# Adafruit_EZ-Key_Breakout.net
KiCad netlist of a schematic drawn in EAGLE
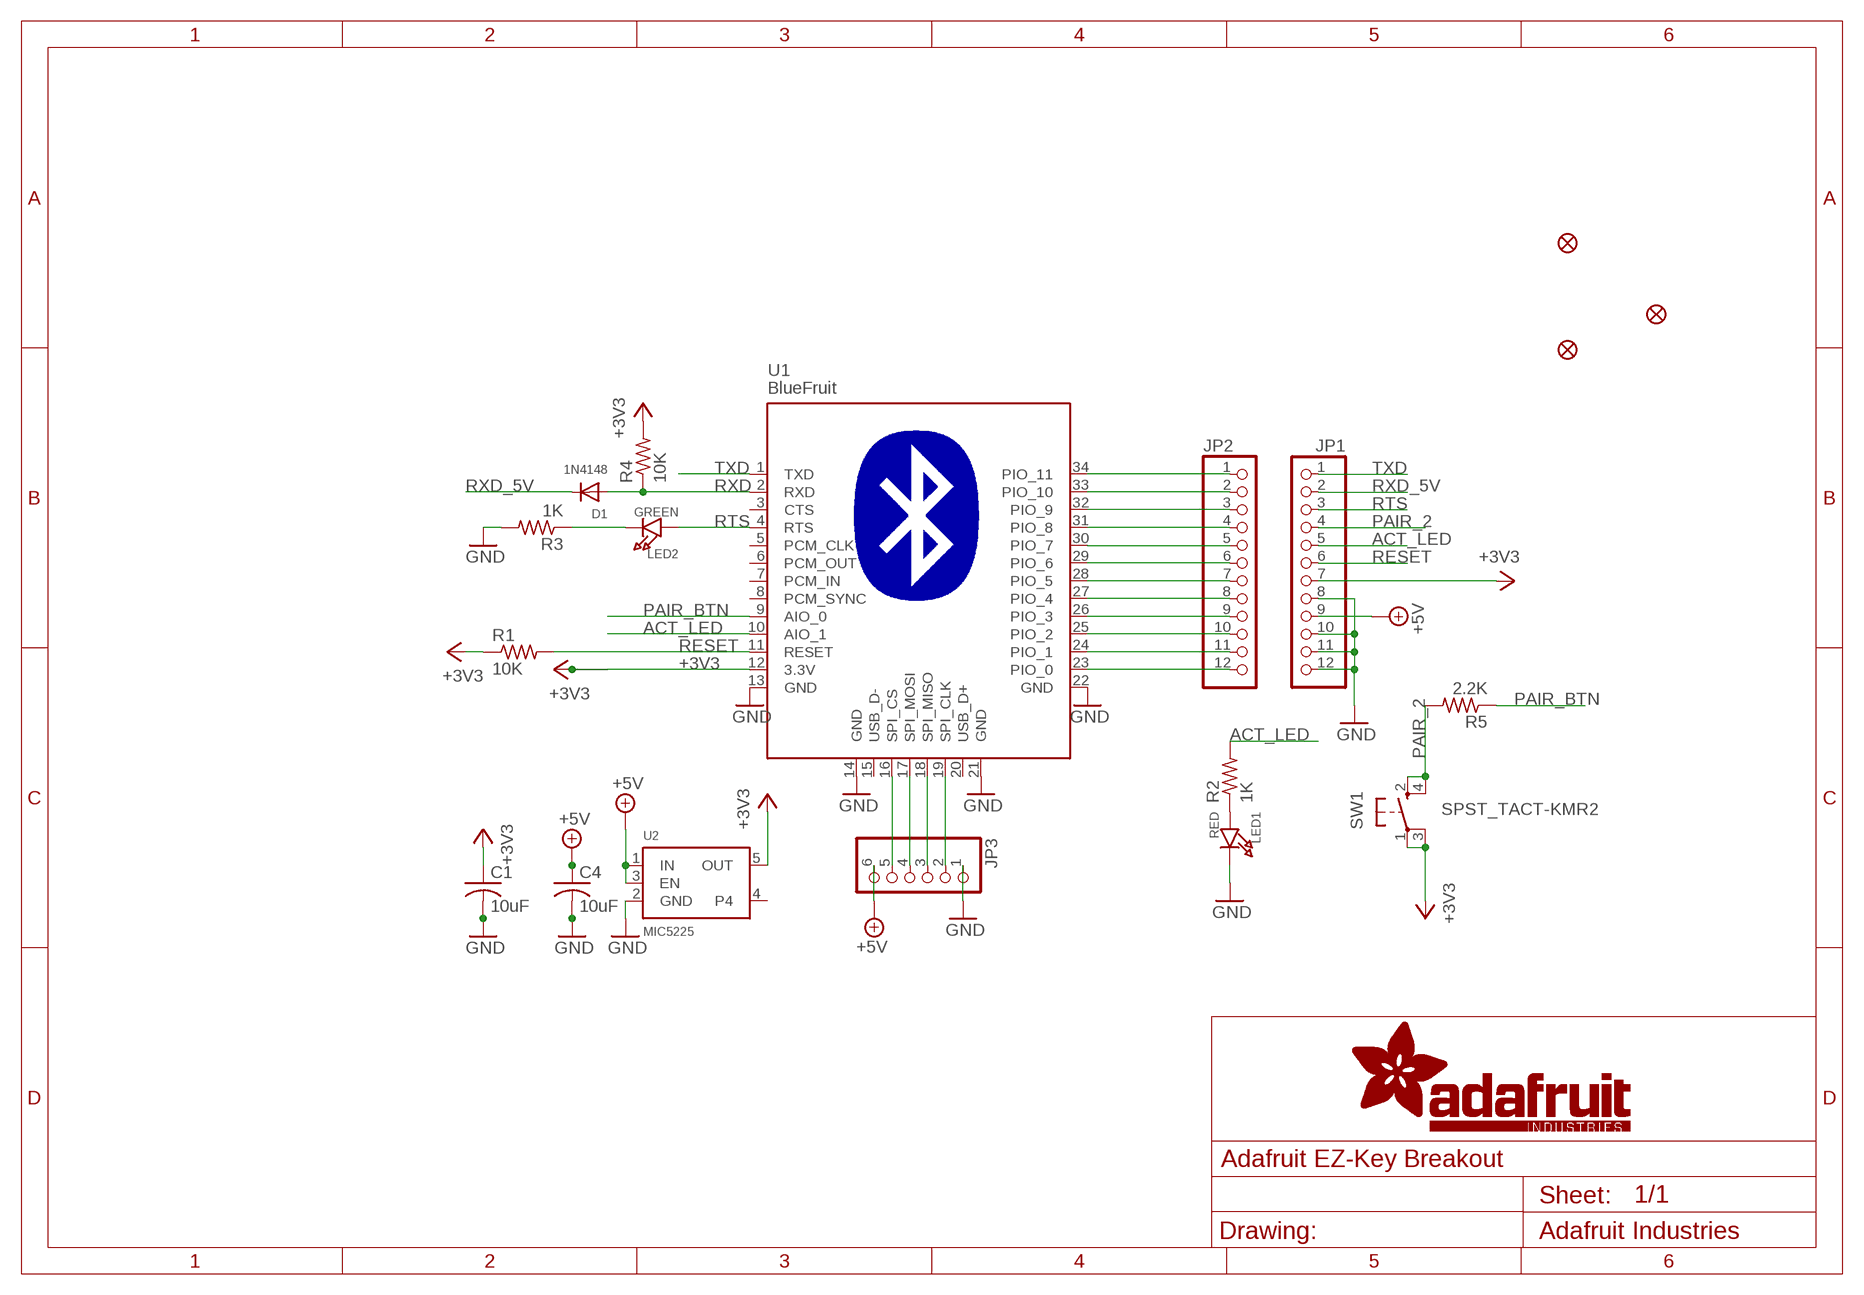
[diagram p0: schematic, sheet 1]

(export (version "E")
  (design (tool "Eeschema 10.0.6"))
  (components
    (comp (ref "C1")
      (value "10uF")
      (footprint "eagle-import:C0805")
      (libsource (lib "eagle-import") (part "C-USC0805"))
    )
    (comp (ref "C4")
      (value "10uF")
      (footprint "eagle-import:C0805")
      (libsource (lib "eagle-import") (part "C-USC0805"))
    )
    (comp (ref "D1")
      (value "1N4148")
      (footprint "eagle-import:SOD-323")
      (libsource (lib "eagle-import") (part "DIODESOD-323"))
    )
    (comp (ref "FID1")
      (value "FIDUCIAL\"\"")
      (footprint "eagle-import:FIDUCIAL_1MM")
      (libsource (lib "eagle-import") (part "FIDUCIAL{dblquote}{dblquote}"))
    )
    (comp (ref "FID2")
      (value "FIDUCIAL\"\"")
      (footprint "eagle-import:FIDUCIAL_1MM")
      (libsource (lib "eagle-import") (part "FIDUCIAL{dblquote}{dblquote}"))
    )
    (comp (ref "FID3")
      (value "FIDUCIAL\"\"")
      (footprint "eagle-import:FIDUCIAL_1MM")
      (libsource (lib "eagle-import") (part "FIDUCIAL{dblquote}{dblquote}"))
    )
    (comp (ref "JP1")
      (value "PINHD-1X12-CB")
      (footprint "eagle-import:1X12-CB")
      (libsource (lib "eagle-import") (part "PINHD-1X12-CB"))
    )
    (comp (ref "JP2")
      (value "PINHD-1X12-CB")
      (footprint "eagle-import:1X12-CB")
      (libsource (lib "eagle-import") (part "PINHD-1X12-CB"))
    )
    (comp (ref "JP3")
      (value "PINHD-1X6B")
      (footprint "eagle-import:1X06-BIG")
      (libsource (lib "eagle-import") (part "PINHD-1X6B"))
    )
    (comp (ref "LED1")
      (value "RED")
      (footprint "eagle-import:CHIPLED_0805_NOOUTLINE")
      (libsource (lib "eagle-import") (part "LED0805_NOOUTLINE"))
    )
    (comp (ref "LED2")
      (value "GREEN")
      (footprint "eagle-import:CHIPLED_0805_NOOUTLINE")
      (libsource (lib "eagle-import") (part "LED0805_NOOUTLINE"))
    )
    (comp (ref "R1")
      (value "10K")
      (footprint "eagle-import:R0805")
      (libsource (lib "eagle-import") (part "R-US_R0805"))
    )
    (comp (ref "R2")
      (value "1K")
      (footprint "eagle-import:R0805")
      (libsource (lib "eagle-import") (part "R-US_R0805"))
    )
    (comp (ref "R3")
      (value "1K")
      (footprint "eagle-import:R0805")
      (libsource (lib "eagle-import") (part "R-US_R0805"))
    )
    (comp (ref "R4")
      (value "10K")
      (footprint "eagle-import:R0805")
      (libsource (lib "eagle-import") (part "R-US_R0805"))
    )
    (comp (ref "R5")
      (value "2.2K")
      (footprint "eagle-import:R0805")
      (libsource (lib "eagle-import") (part "R-US_R0805"))
    )
    (comp (ref "SW1")
      (value "SPST_TACT-KMR2")
      (footprint "eagle-import:KMR2")
      (libsource (lib "eagle-import") (part "SPST_TACT-KMR2"))
    )
    (comp (ref "U1")
      (value "BlueFruit")
      (footprint "eagle-import:BLUETOOTH_MODULE")
      (libsource (lib "eagle-import") (part "BLUETOOTH_MODULE"))
    )
    (comp (ref "U2")
      (value "MIC5225")
      (footprint "eagle-import:SOT23-5")
      (libsource (lib "eagle-import") (part "VREG_SOT23-5"))
    )
  )
  (nets
    (net (code "1") (name "+3V3") (class "Default")
      (node (ref "C1") (pin "1") (pinfunction "1_1") (pintype "passive"))
      (node (ref "JP1") (pin "7") (pinfunction "7_7") (pintype "passive"))
      (node (ref "R1") (pin "1") (pinfunction "1_1") (pintype "passive"))
      (node (ref "R4") (pin "2") (pinfunction "2_2") (pintype "passive"))
      (node (ref "SW1") (pin "1") (pinfunction "P_1") (pintype "passive"))
      (node (ref "SW1") (pin "3") (pinfunction "P1_3") (pintype "passive"))
      (node (ref "U1") (pin "12") (pinfunction "3.3V_12") (pintype "power_in"))
      (node (ref "U2") (pin "5") (pinfunction "OUT_5") (pintype "power_in"))
    )
    (net (code "2") (name "+5V") (class "Default")
      (node (ref "C4") (pin "1") (pinfunction "1_1") (pintype "passive"))
      (node (ref "JP1") (pin "9") (pinfunction "9_9") (pintype "passive"))
      (node (ref "JP3") (pin "6") (pinfunction "6_6") (pintype "passive"))
      (node (ref "U2") (pin "1") (pinfunction "IN_1") (pintype "power_in"))
      (node (ref "U2") (pin "3") (pinfunction "EN_3") (pintype "input"))
    )
    (net (code "3") (name "/ACT_LED") (class "Default")
      (node (ref "JP1") (pin "5") (pinfunction "5_5") (pintype "passive"))
      (node (ref "R2") (pin "2") (pinfunction "2_2") (pintype "passive"))
      (node (ref "U1") (pin "10") (pinfunction "AIO_1_10") (pintype "bidirectional"))
    )
    (net (code "4") (name "/PAIR_2") (class "Default")
      (node (ref "JP1") (pin "4") (pinfunction "4_4") (pintype "passive"))
      (node (ref "R5") (pin "2") (pinfunction "2_2") (pintype "passive"))
      (node (ref "SW1") (pin "2") (pinfunction "S_2") (pintype "passive"))
      (node (ref "SW1") (pin "4") (pinfunction "S1_4") (pintype "passive"))
    )
    (net (code "5") (name "/PAIR_BTN") (class "Default")
      (node (ref "R5") (pin "1") (pinfunction "1_1") (pintype "passive"))
      (node (ref "U1") (pin "9") (pinfunction "AIO_0_9") (pintype "bidirectional"))
    )
    (net (code "6") (name "/RESET") (class "Default")
      (node (ref "JP1") (pin "6") (pinfunction "6_6") (pintype "passive"))
      (node (ref "R1") (pin "2") (pinfunction "2_2") (pintype "passive"))
      (node (ref "U1") (pin "11") (pinfunction "RESET_11") (pintype "bidirectional"))
    )
    (net (code "7") (name "/RTS") (class "Default")
      (node (ref "JP1") (pin "3") (pinfunction "3_3") (pintype "passive"))
      (node (ref "LED2") (pin "A") (pinfunction "A_A") (pintype "passive"))
      (node (ref "U1") (pin "4") (pinfunction "RTS_4") (pintype "bidirectional"))
    )
    (net (code "8") (name "/RXD") (class "Default")
      (node (ref "D1") (pin "A") (pinfunction "A_A") (pintype "passive"))
      (node (ref "R4") (pin "1") (pinfunction "1_1") (pintype "passive"))
      (node (ref "U1") (pin "2") (pinfunction "RXD_2") (pintype "bidirectional"))
    )
    (net (code "9") (name "/RXD_5V") (class "Default")
      (node (ref "D1") (pin "C") (pinfunction "C_C") (pintype "passive"))
      (node (ref "JP1") (pin "2") (pinfunction "2_2") (pintype "passive"))
    )
    (net (code "10") (name "/TXD") (class "Default")
      (node (ref "JP1") (pin "1") (pinfunction "1_1") (pintype "passive"))
      (node (ref "U1") (pin "1") (pinfunction "TXD_1") (pintype "bidirectional"))
    )
    (net (code "11") (name "GND") (class "Default")
      (node (ref "C1") (pin "2") (pinfunction "2_2") (pintype "passive"))
      (node (ref "C4") (pin "2") (pinfunction "2_2") (pintype "passive"))
      (node (ref "JP1") (pin "10") (pinfunction "10_10") (pintype "passive"))
      (node (ref "JP1") (pin "11") (pinfunction "11_11") (pintype "passive"))
      (node (ref "JP1") (pin "12") (pinfunction "12_12") (pintype "passive"))
      (node (ref "JP1") (pin "8") (pinfunction "8_8") (pintype "passive"))
      (node (ref "JP3") (pin "1") (pinfunction "1_1") (pintype "passive"))
      (node (ref "LED1") (pin "C") (pinfunction "C_C") (pintype "passive"))
      (node (ref "R3") (pin "2") (pinfunction "2_2") (pintype "passive"))
      (node (ref "U1") (pin "13") (pinfunction "GND_13") (pintype "power_in"))
      (node (ref "U1") (pin "14") (pinfunction "GND_14") (pintype "power_in"))
      (node (ref "U1") (pin "21") (pinfunction "GND_21") (pintype "power_in"))
      (node (ref "U1") (pin "22") (pinfunction "GND_22") (pintype "power_in"))
      (node (ref "U2") (pin "2") (pinfunction "GND_2") (pintype "power_in"))
    )
    (net (code "12") (name "Net-(LED1-PadA)") (class "Default")
      (node (ref "LED1") (pin "A") (pinfunction "A_A") (pintype "passive"))
      (node (ref "R2") (pin "1") (pinfunction "1_1") (pintype "passive"))
    )
    (net (code "13") (name "Net-(LED2-PadC)") (class "Default")
      (node (ref "LED2") (pin "C") (pinfunction "C_C") (pintype "passive"))
      (node (ref "R3") (pin "1") (pinfunction "1_1") (pintype "passive"))
    )
    (net (code "14") (name "Net-(U1-PIO_0)") (class "Default")
      (node (ref "JP2") (pin "12") (pinfunction "12_12") (pintype "passive"))
      (node (ref "U1") (pin "23") (pinfunction "PIO_0_23") (pintype "bidirectional"))
    )
    (net (code "15") (name "Net-(U1-PIO_1)") (class "Default")
      (node (ref "JP2") (pin "11") (pinfunction "11_11") (pintype "passive"))
      (node (ref "U1") (pin "24") (pinfunction "PIO_1_24") (pintype "bidirectional"))
    )
    (net (code "16") (name "Net-(U1-PIO_2)") (class "Default")
      (node (ref "JP2") (pin "10") (pinfunction "10_10") (pintype "passive"))
      (node (ref "U1") (pin "25") (pinfunction "PIO_2_25") (pintype "bidirectional"))
    )
    (net (code "17") (name "Net-(U1-PIO_3)") (class "Default")
      (node (ref "JP2") (pin "9") (pinfunction "9_9") (pintype "passive"))
      (node (ref "U1") (pin "26") (pinfunction "PIO_3_26") (pintype "bidirectional"))
    )
    (net (code "18") (name "Net-(U1-PIO_4)") (class "Default")
      (node (ref "JP2") (pin "8") (pinfunction "8_8") (pintype "passive"))
      (node (ref "U1") (pin "27") (pinfunction "PIO_4_27") (pintype "bidirectional"))
    )
    (net (code "19") (name "Net-(U1-PIO_5)") (class "Default")
      (node (ref "JP2") (pin "7") (pinfunction "7_7") (pintype "passive"))
      (node (ref "U1") (pin "28") (pinfunction "PIO_5_28") (pintype "bidirectional"))
    )
    (net (code "20") (name "Net-(U1-PIO_6)") (class "Default")
      (node (ref "JP2") (pin "6") (pinfunction "6_6") (pintype "passive"))
      (node (ref "U1") (pin "29") (pinfunction "PIO_6_29") (pintype "bidirectional"))
    )
    (net (code "21") (name "Net-(U1-PIO_7)") (class "Default")
      (node (ref "JP2") (pin "5") (pinfunction "5_5") (pintype "passive"))
      (node (ref "U1") (pin "30") (pinfunction "PIO_7_30") (pintype "bidirectional"))
    )
    (net (code "22") (name "Net-(U1-PIO_8)") (class "Default")
      (node (ref "JP2") (pin "4") (pinfunction "4_4") (pintype "passive"))
      (node (ref "U1") (pin "31") (pinfunction "PIO_8_31") (pintype "bidirectional"))
    )
    (net (code "23") (name "Net-(U1-PIO_9)") (class "Default")
      (node (ref "JP2") (pin "3") (pinfunction "3_3") (pintype "passive"))
      (node (ref "U1") (pin "32") (pinfunction "PIO_9_32") (pintype "bidirectional"))
    )
    (net (code "24") (name "Net-(U1-PIO_10)") (class "Default")
      (node (ref "JP2") (pin "2") (pinfunction "2_2") (pintype "passive"))
      (node (ref "U1") (pin "33") (pinfunction "PIO_10_33") (pintype "bidirectional"))
    )
    (net (code "25") (name "Net-(U1-PIO_11)") (class "Default")
      (node (ref "JP2") (pin "1") (pinfunction "1_1") (pintype "passive"))
      (node (ref "U1") (pin "34") (pinfunction "PIO_11_34") (pintype "bidirectional"))
    )
    (net (code "26") (name "Net-(U1-SPI_CLK)") (class "Default")
      (node (ref "JP3") (pin "2") (pinfunction "2_2") (pintype "passive"))
      (node (ref "U1") (pin "19") (pinfunction "SPI_CLK_19") (pintype "bidirectional"))
    )
    (net (code "27") (name "Net-(U1-SPI_CS)") (class "Default")
      (node (ref "JP3") (pin "5") (pinfunction "5_5") (pintype "passive"))
      (node (ref "U1") (pin "16") (pinfunction "SPI_CS_16") (pintype "bidirectional"))
    )
    (net (code "28") (name "Net-(U1-SPI_MISO)") (class "Default")
      (node (ref "JP3") (pin "3") (pinfunction "3_3") (pintype "passive"))
      (node (ref "U1") (pin "18") (pinfunction "SPI_MISO_18") (pintype "bidirectional"))
    )
    (net (code "29") (name "Net-(U1-SPI_MOSI)") (class "Default")
      (node (ref "JP3") (pin "4") (pinfunction "4_4") (pintype "passive"))
      (node (ref "U1") (pin "17") (pinfunction "SPI_MOSI_17") (pintype "bidirectional"))
    )
    (net (code "30") (name "unconnected-(U1-CTS-Pad3)") (class "Default")
      (node (ref "U1") (pin "3") (pinfunction "CTS_3") (pintype "bidirectional"))
    )
    (net (code "31") (name "unconnected-(U1-PCM_CLK-Pad5)") (class "Default")
      (node (ref "U1") (pin "5") (pinfunction "PCM_CLK_5") (pintype "bidirectional"))
    )
    (net (code "32") (name "unconnected-(U1-PCM_IN-Pad7)") (class "Default")
      (node (ref "U1") (pin "7") (pinfunction "PCM_IN_7") (pintype "bidirectional"))
    )
    (net (code "33") (name "unconnected-(U1-PCM_OUT-Pad6)") (class "Default")
      (node (ref "U1") (pin "6") (pinfunction "PCM_OUT_6") (pintype "bidirectional"))
    )
    (net (code "34") (name "unconnected-(U1-PCM_SYNC-Pad8)") (class "Default")
      (node (ref "U1") (pin "8") (pinfunction "PCM_SYNC_8") (pintype "bidirectional"))
    )
    (net (code "35") (name "unconnected-(U1-USB_D+-Pad20)") (class "Default")
      (node (ref "U1") (pin "20") (pinfunction "USB_D+_20") (pintype "bidirectional"))
    )
    (net (code "36") (name "unconnected-(U1-USB_D--Pad15)") (class "Default")
      (node (ref "U1") (pin "15") (pinfunction "USB_D-_15") (pintype "bidirectional"))
    )
    (net (code "37") (name "unconnected-(U2-P4-Pad4)") (class "Default")
      (node (ref "U2") (pin "4") (pinfunction "P4_4") (pintype "bidirectional"))
    )
  )
)
